# TPS40057.net
KiCad netlist of a schematic drawn in Altium Designer
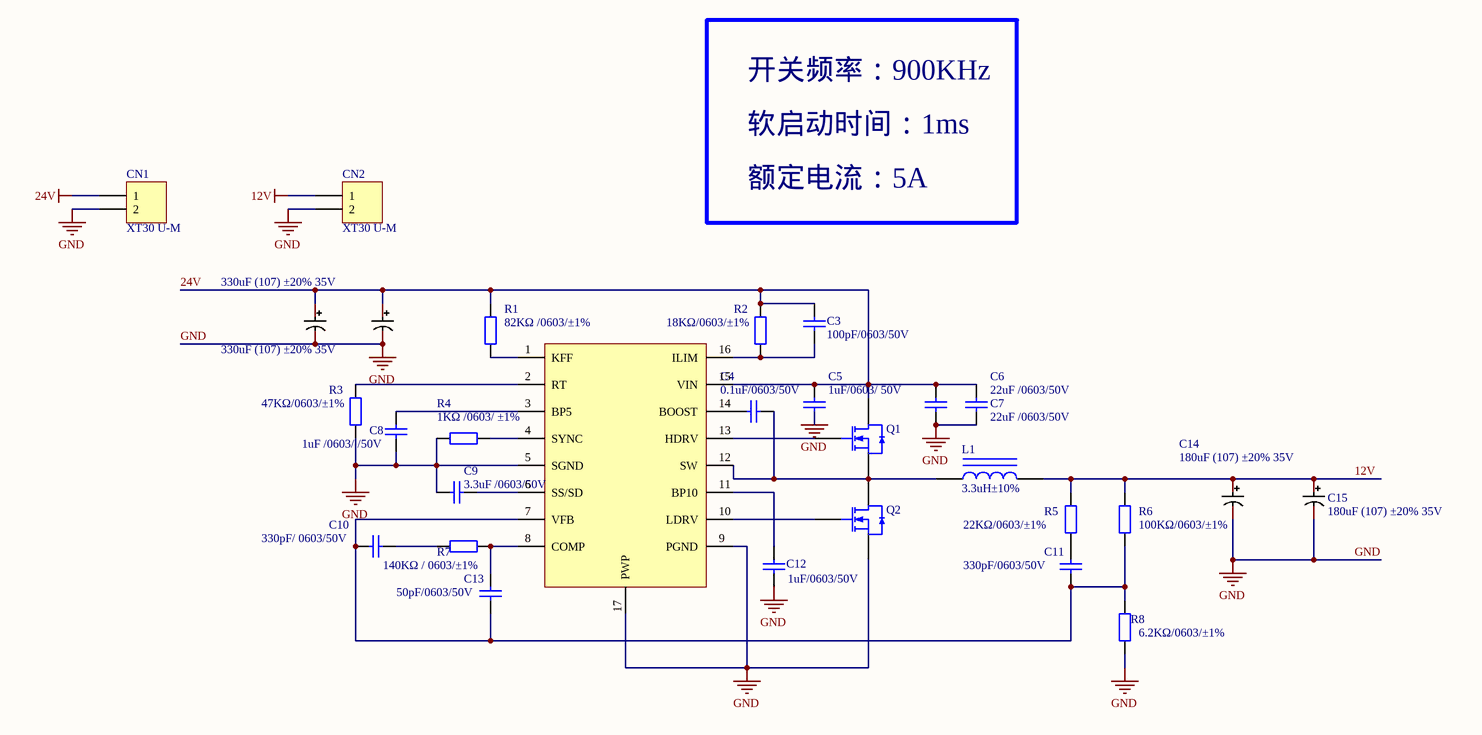
[diagram p0: TPS40057.SchDoc]

(export (version "E")
  (design (tool "Eeschema 10.0.6"))
  (components
    (comp (ref "C1")
      (value "330uF (107) ±20% 35V")
      (footprint "CAP-SMD_BD10.0-L10.3-W10.3-LS11.3-FD")
      (description "电解电容")
      (fields (field (name "MANUFACTURER") "ROQANG(容强)") (field (name "MANUFACTURER PART") "RVT1V331M1010"))
      (libsource (lib "TPS40057") (part "330uF (107) ±20% 35V"))
    )
    (comp (ref "C2")
      (value "330uF (107) ±20% 35V")
      (footprint "CAP-SMD_BD10.0-L10.3-W10.3-LS11.3-FD")
      (description "电解电容")
      (fields (field (name "MANUFACTURER") "ROQANG(容强)") (field (name "MANUFACTURER PART") "RVT1V331M1010"))
      (libsource (lib "TPS40057") (part "330uF (107) ±20% 35V"))
    )
    (comp (ref "C3")
      (value "100pF/0603/50V")
      (footprint "0603_C")
      (description "贴片电容")
      (libsource (lib "TPS40057") (part "0603 22pF (220) 5% 50V"))
    )
    (comp (ref "C4")
      (value "0.1uF/0603/50V")
      (footprint "0603_C")
      (description "贴片电容")
      (libsource (lib "TPS40057") (part "0603 22pF (220) 5% 50V"))
    )
    (comp (ref "C5")
      (value "1uF/0603/ 50V")
      (footprint "0603_C")
      (description "贴片电容")
      (libsource (lib "TPS40057") (part "0603 22pF (220) 5% 50V"))
    )
    (comp (ref "C6")
      (value "22uF /0603/50V")
      (footprint "0603_C")
      (description "贴片电容")
      (libsource (lib "TPS40057") (part "0603 22pF (220) 5% 50V"))
    )
    (comp (ref "C7")
      (value "22uF /0603/50V")
      (footprint "0603_C")
      (description "贴片电容")
      (libsource (lib "TPS40057") (part "0603 22pF (220) 5% 50V"))
    )
    (comp (ref "C8")
      (value "1uF /0603/ /50V")
      (footprint "0603_C")
      (description "贴片电容")
      (libsource (lib "TPS40057") (part "0603 22pF (220) 5% 50V"))
    )
    (comp (ref "C9")
      (value "3.3uF /0603/50V")
      (footprint "0603_C")
      (description "贴片电容")
      (libsource (lib "TPS40057") (part "0603 22pF (220) 5% 50V"))
    )
    (comp (ref "C10")
      (value "330pF/ 0603/50V")
      (footprint "0603_C")
      (description "贴片电容")
      (libsource (lib "TPS40057") (part "0603 22pF (220) 5% 50V"))
    )
    (comp (ref "C11")
      (value "330pF/0603/50V")
      (footprint "0603_C")
      (description "贴片电容")
      (libsource (lib "TPS40057") (part "0603 22pF (220) 5% 50V"))
    )
    (comp (ref "C12")
      (value "1uF/0603/50V")
      (footprint "0603_C")
      (description "贴片电容")
      (libsource (lib "TPS40057") (part "0603 22pF (220) 5% 50V"))
    )
    (comp (ref "C13")
      (value "50pF/0603/50V")
      (footprint "0603_C")
      (description "贴片电容")
      (libsource (lib "TPS40057") (part "0603 22pF (220) 5% 50V"))
    )
    (comp (ref "C14")
      (value "180uF (107) ±20% 35V")
      (footprint "CAP-SMD_BD8.0-L8.3-W8.3-FD")
      (description "电解电容")
      (libsource (lib "TPS40057") (part "180uF (107) ±20% 35V"))
    )
    (comp (ref "C15")
      (value "180uF (107) ±20% 35V")
      (footprint "CAP-SMD_BD8.0-L8.3-W8.3-FD")
      (description "电解电容")
      (libsource (lib "TPS40057") (part "180uF (107) ±20% 35V"))
    )
    (comp (ref "CN1")
      (value "XT30 U-M")
      (footprint "CONN-TH_XT30U-M")
      (description "模型插头轻量版锂电池插头")
      (libsource (lib "TPS40057") (part "XT30 U-M"))
    )
    (comp (ref "CN2")
      (value "XT30 U-M")
      (footprint "CONN-TH_XT30U-M")
      (description "模型插头轻量版锂电池插头")
      (libsource (lib "TPS40057") (part "XT30 U-M"))
    )
    (comp (ref "L1")
      (value "3.3uH±10%")
      (footprint "IND-SMD_L7.0-W6.6")
      (description "贴片电感")
      (libsource (lib "TPS40057") (part "0805 3.3uH10%"))
    )
    (comp (ref "Q1")
      (value "ST3422A N道沟 SOT-23")
      (footprint "SOT-23-3_L2.9-W1.6-P1.90-LS2.8-BR")
      (description "MOS(场效应管)")
      (libsource (lib "TPS40057") (part "ST3422A N道沟  SOT-23"))
    )
    (comp (ref "Q2")
      (value "ST3422A N道沟 SOT-23")
      (footprint "SOT-23-3_L2.9-W1.6-P1.90-LS2.8-BR")
      (description "MOS(场效应管)")
      (libsource (lib "TPS40057") (part "ST3422A N道沟  SOT-23"))
    )
    (comp (ref "R1")
      (value "82KΩ /0603/±1%")
      (footprint "0603_R")
      (description "贴片电阻")
      (libsource (lib "TPS40057") (part "0603 10KΩ (1002) 1%_1"))
    )
    (comp (ref "R2")
      (value "18KΩ/0603/±1%")
      (footprint "0603_R")
      (description "贴片电阻")
      (libsource (lib "TPS40057") (part "0603 10KΩ (1002) 1%_1"))
    )
    (comp (ref "R3")
      (value "47KΩ/0603/±1%")
      (footprint "0603_R")
      (description "贴片电阻")
      (libsource (lib "TPS40057") (part "0603 10KΩ (1002) 1%_1"))
    )
    (comp (ref "R4")
      (value "1KΩ /0603/ ±1%")
      (footprint "0603_R")
      (description "贴片电阻")
      (libsource (lib "") (part "0603 10KΩ (1002) 1%_1_1"))
    )
    (comp (ref "R5")
      (value "22KΩ/0603/±1%")
      (footprint "0603_R")
      (description "贴片电阻")
      (libsource (lib "TPS40057") (part "0603 10KΩ (1002) 1%_1"))
    )
    (comp (ref "R6")
      (value "100KΩ/0603/±1%")
      (footprint "0603_R")
      (description "贴片电阻")
      (libsource (lib "TPS40057") (part "0603 10KΩ (1002) 1%_1"))
    )
    (comp (ref "R7")
      (value "140KΩ / 0603/±1%")
      (footprint "0603_R")
      (description "贴片电阻")
      (libsource (lib "") (part "0603 10KΩ (1002) 1%_1_1"))
    )
    (comp (ref "R8")
      (value "6.2KΩ/0603/±1%")
      (footprint "0603_R")
      (description "贴片电阻")
      (libsource (lib "TPS40057") (part "0603 10KΩ (1002) 1%_1"))
    )
    (comp (ref "U1")
      (value "TPS40057PWP")
      (footprint "TSSOP-16_L5.0-W4.4-P0.65-LS6.4-BL-EP")
      (description "电源IC")
      (fields (field (name "MANUFACTURER") "TI(德州仪器)"))
      (libsource (lib "TPS40057") (part "TPS40057PWPR"))
    )
  )
  (nets
    (net (code "1") (name "12V") (class "Default")
      (node (ref "C14") (pin "1") (pinfunction "1_1") (pintype "passive"))
      (node (ref "C15") (pin "1") (pinfunction "1_1") (pintype "passive"))
      (node (ref "CN2") (pin "1") (pinfunction "1_1") (pintype "passive"))
      (node (ref "L1") (pin "2") (pinfunction "2_2") (pintype "passive"))
      (node (ref "R5") (pin "2") (pinfunction "2_2") (pintype "passive"))
      (node (ref "R6") (pin "2") (pinfunction "2_2") (pintype "passive"))
    )
    (net (code "2") (name "24V") (class "Default")
      (node (ref "C1") (pin "1") (pinfunction "1_1") (pintype "passive"))
      (node (ref "C2") (pin "1") (pinfunction "1_1") (pintype "passive"))
      (node (ref "C3") (pin "2") (pinfunction "2_2") (pintype "passive"))
      (node (ref "C5") (pin "2") (pinfunction "2_2") (pintype "passive"))
      (node (ref "C6") (pin "2") (pinfunction "2_2") (pintype "passive"))
      (node (ref "C7") (pin "2") (pinfunction "2_2") (pintype "passive"))
      (node (ref "CN1") (pin "1") (pinfunction "1_1") (pintype "passive"))
      (node (ref "Q1") (pin "3") (pinfunction "D_3") (pintype "passive"))
      (node (ref "R1") (pin "2") (pinfunction "2_2") (pintype "passive"))
      (node (ref "R2") (pin "2") (pinfunction "2_2") (pintype "passive"))
      (node (ref "U1") (pin "15") (pinfunction "VIN_15") (pintype "passive"))
    )
    (net (code "3") (name "GND") (class "Default")
      (node (ref "C1") (pin "2") (pinfunction "2_2") (pintype "passive"))
      (node (ref "C12") (pin "1") (pinfunction "1_1") (pintype "passive"))
      (node (ref "C14") (pin "2") (pinfunction "2_2") (pintype "passive"))
      (node (ref "C15") (pin "2") (pinfunction "2_2") (pintype "passive"))
      (node (ref "C2") (pin "2") (pinfunction "2_2") (pintype "passive"))
      (node (ref "C5") (pin "1") (pinfunction "1_1") (pintype "passive"))
      (node (ref "C6") (pin "1") (pinfunction "1_1") (pintype "passive"))
      (node (ref "C7") (pin "1") (pinfunction "1_1") (pintype "passive"))
      (node (ref "C8") (pin "1") (pinfunction "1_1") (pintype "passive"))
      (node (ref "C9") (pin "2") (pinfunction "2_2") (pintype "passive"))
      (node (ref "CN1") (pin "2") (pinfunction "2_2") (pintype "passive"))
      (node (ref "CN2") (pin "2") (pinfunction "2_2") (pintype "passive"))
      (node (ref "Q2") (pin "2") (pinfunction "S_2") (pintype "passive"))
      (node (ref "R3") (pin "1") (pinfunction "1_1") (pintype "passive"))
      (node (ref "R4") (pin "2") (pinfunction "2_2") (pintype "passive"))
      (node (ref "R8") (pin "1") (pinfunction "1_1") (pintype "passive"))
      (node (ref "U1") (pin "17") (pinfunction "PWP_17") (pintype "passive"))
      (node (ref "U1") (pin "5") (pinfunction "SGND_5") (pintype "passive"))
      (node (ref "U1") (pin "9") (pinfunction "PGND_9") (pintype "passive"))
    )
    (net (code "4") (name "Net-(C10-Pad1)") (class "Default")
      (node (ref "C10") (pin "1") (pinfunction "1_1") (pintype "passive"))
      (node (ref "R7") (pin "2") (pinfunction "2_2") (pintype "passive"))
    )
    (net (code "5") (name "Net-(C11-Pad2)") (class "Default")
      (node (ref "C11") (pin "2") (pinfunction "2_2") (pintype "passive"))
      (node (ref "R5") (pin "1") (pinfunction "1_1") (pintype "passive"))
    )
    (net (code "6") (name "Net-(Q1-G)") (class "Default")
      (node (ref "Q1") (pin "1") (pinfunction "G_1") (pintype "passive"))
      (node (ref "U1") (pin "13") (pinfunction "HDRV_13") (pintype "passive"))
    )
    (net (code "7") (name "Net-(Q1-S)") (class "Default")
      (node (ref "C4") (pin "1") (pinfunction "1_1") (pintype "passive"))
      (node (ref "L1") (pin "1") (pinfunction "1_1") (pintype "passive"))
      (node (ref "Q1") (pin "2") (pinfunction "S_2") (pintype "passive"))
      (node (ref "Q2") (pin "3") (pinfunction "D_3") (pintype "passive"))
      (node (ref "U1") (pin "12") (pinfunction "SW_12") (pintype "passive"))
    )
    (net (code "8") (name "Net-(Q2-G)") (class "Default")
      (node (ref "Q2") (pin "1") (pinfunction "G_1") (pintype "passive"))
      (node (ref "U1") (pin "10") (pinfunction "LDRV_10") (pintype "passive"))
    )
    (net (code "9") (name "Net-(U1-BOOST)") (class "Default")
      (node (ref "C4") (pin "2") (pinfunction "2_2") (pintype "passive"))
      (node (ref "U1") (pin "14") (pinfunction "BOOST_14") (pintype "passive"))
    )
    (net (code "10") (name "Net-(U1-BP5)") (class "Default")
      (node (ref "C8") (pin "2") (pinfunction "2_2") (pintype "passive"))
      (node (ref "U1") (pin "3") (pinfunction "BP5_3") (pintype "passive"))
    )
    (net (code "11") (name "Net-(U1-BP10)") (class "Default")
      (node (ref "C12") (pin "2") (pinfunction "2_2") (pintype "passive"))
      (node (ref "U1") (pin "11") (pinfunction "BP10_11") (pintype "passive"))
    )
    (net (code "12") (name "Net-(U1-COMP)") (class "Default")
      (node (ref "C13") (pin "2") (pinfunction "2_2") (pintype "passive"))
      (node (ref "R7") (pin "1") (pinfunction "1_1") (pintype "passive"))
      (node (ref "U1") (pin "8") (pinfunction "COMP_8") (pintype "passive"))
    )
    (net (code "13") (name "Net-(U1-ILIM)") (class "Default")
      (node (ref "C3") (pin "1") (pinfunction "1_1") (pintype "passive"))
      (node (ref "R2") (pin "1") (pinfunction "1_1") (pintype "passive"))
      (node (ref "U1") (pin "16") (pinfunction "ILIM_16") (pintype "passive"))
    )
    (net (code "14") (name "Net-(U1-KFF)") (class "Default")
      (node (ref "R1") (pin "1") (pinfunction "1_1") (pintype "passive"))
      (node (ref "U1") (pin "1") (pinfunction "KFF_1") (pintype "passive"))
    )
    (net (code "15") (name "Net-(U1-RT)") (class "Default")
      (node (ref "R3") (pin "2") (pinfunction "2_2") (pintype "passive"))
      (node (ref "U1") (pin "2") (pinfunction "RT_2") (pintype "passive"))
    )
    (net (code "16") (name "Net-(U1-SS{slash}SD)") (class "Default")
      (node (ref "C9") (pin "1") (pinfunction "1_1") (pintype "passive"))
      (node (ref "U1") (pin "6") (pinfunction "SS/SD_6") (pintype "passive"))
    )
    (net (code "17") (name "Net-(U1-SYNC)") (class "Default")
      (node (ref "R4") (pin "1") (pinfunction "1_1") (pintype "passive"))
      (node (ref "U1") (pin "4") (pinfunction "SYNC_4") (pintype "passive"))
    )
    (net (code "18") (name "Net-(U1-VFB)") (class "Default")
      (node (ref "C10") (pin "2") (pinfunction "2_2") (pintype "passive"))
      (node (ref "C11") (pin "1") (pinfunction "1_1") (pintype "passive"))
      (node (ref "C13") (pin "1") (pinfunction "1_1") (pintype "passive"))
      (node (ref "R6") (pin "1") (pinfunction "1_1") (pintype "passive"))
      (node (ref "R8") (pin "2") (pinfunction "2_2") (pintype "passive"))
      (node (ref "U1") (pin "7") (pinfunction "VFB_7") (pintype "passive"))
    )
  )
)
